# EntradasAnalogicas.net
KiCad netlist of a schematic drawn in Altium Designer
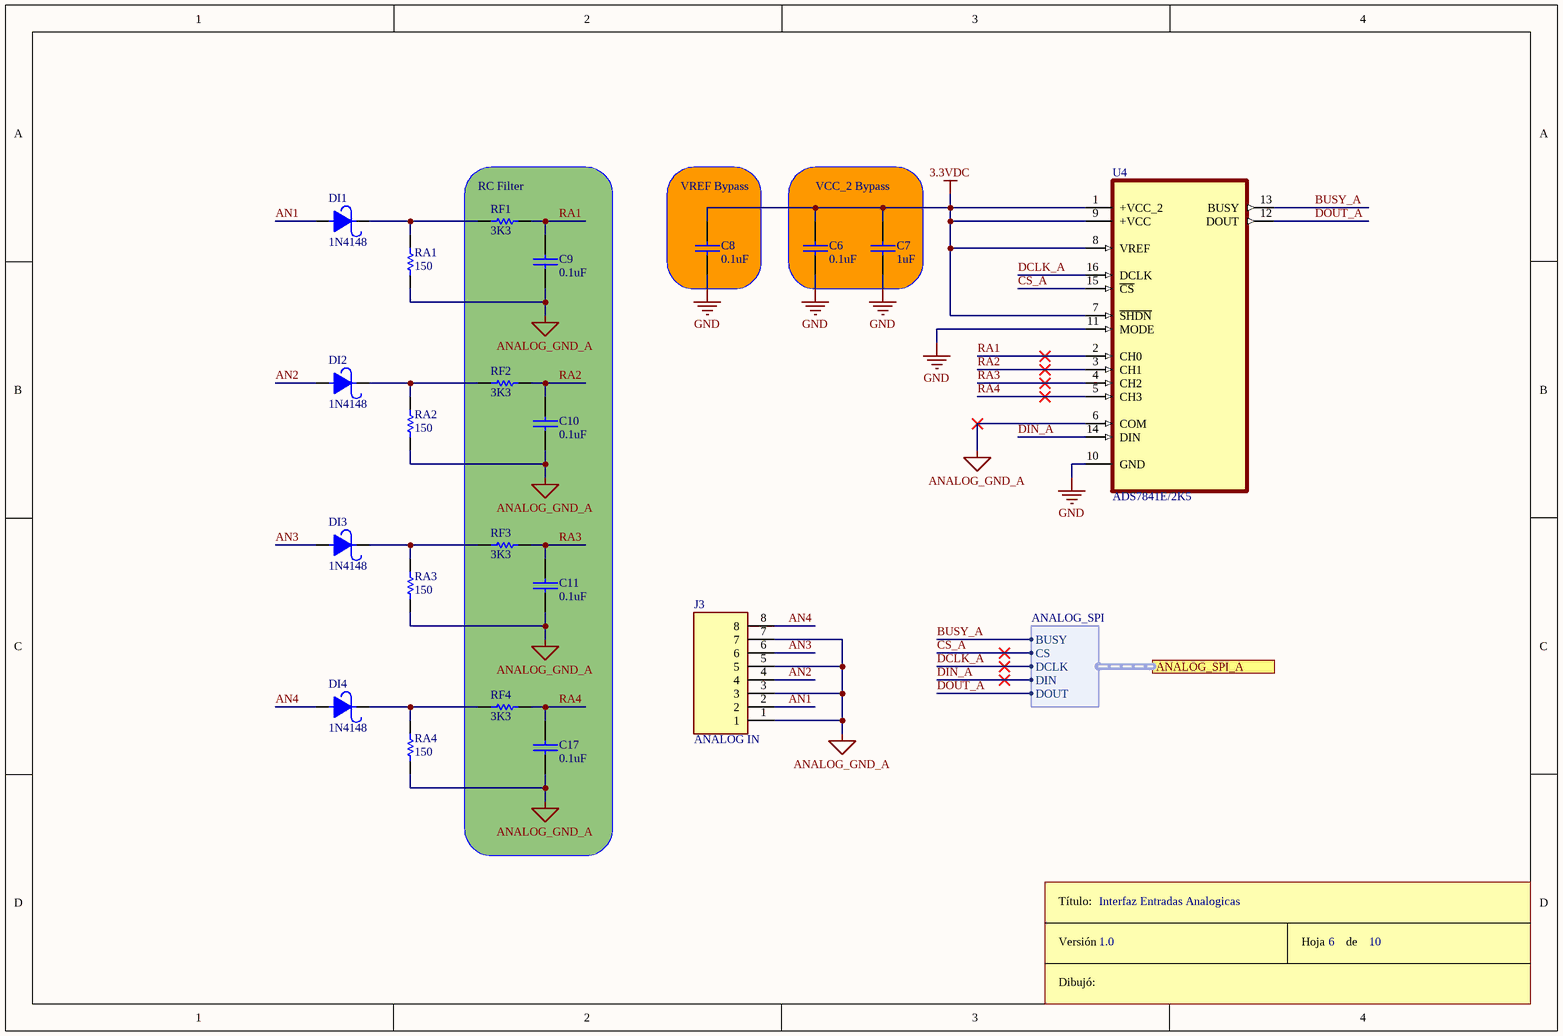
[diagram p0: EntradasAnalogicas.SchDoc]

(export (version "E")
  (design (tool "Eeschema 10.0.6"))
  (components
    (comp (ref "C6") (value "0.1uF") (footprint "CAP100") (libsource (lib "LIBEBAL") (part "CAP")))
    (comp (ref "C7") (value "1uF") (footprint "CAP200") (libsource (lib "LIBEBAL") (part "CAP")))
    (comp (ref "C8") (value "0.1uF") (footprint "CAP100") (libsource (lib "LIBEBAL") (part "CAP")))
    (comp (ref "C9") (value "0.1uF") (footprint "CAP100") (libsource (lib "LIBEBAL") (part "CAP")))
    (comp (ref "C10") (value "0.1uF") (footprint "CAP100") (libsource (lib "LIBEBAL") (part "CAP")))
    (comp (ref "C11") (value "0.1uF") (footprint "CAP100") (libsource (lib "LIBEBAL") (part "CAP")))
    (comp (ref "C17") (value "0.1uF") (footprint "CAP100") (libsource (lib "LIBEBAL") (part "CAP")))
    (comp (ref "DI1") (value "1N4148") (footprint "DO41") (libsource (lib "LIBEBAL") (part "DIODO SCHOTTKY")))
    (comp (ref "DI2") (value "1N4148") (footprint "DO41") (libsource (lib "LIBEBAL") (part "DIODO SCHOTTKY")))
    (comp (ref "DI3") (value "1N4148") (footprint "DO41") (libsource (lib "LIBEBAL") (part "DIODO SCHOTTKY")))
    (comp (ref "DI4") (value "1N4148") (footprint "DO41") (libsource (lib "LIBEBAL") (part "DIODO SCHOTTKY")))
    (comp (ref "J3")
      (value "ANALOG IN")
      (footprint "TE_1586863-8")
      (description "Conn Power HDR 8 POS 4.2mm Solder RA Thru-Hole 8 Terminal 1 Port Tray")
      (fields (field (name "MF") "TE Connectivity") (field (name "MP") "1586863-8"))
      (libsource (lib "MFW8R") (part "1586863-8"))
    )
    (comp (ref "RA1") (value "150") (footprint "RES300") (libsource (lib "LIBEBAL") (part "RES")))
    (comp (ref "RA2") (value "150") (footprint "RES300") (libsource (lib "LIBEBAL") (part "RES")))
    (comp (ref "RA3") (value "150") (footprint "RES300") (libsource (lib "LIBEBAL") (part "RES")))
    (comp (ref "RA4") (value "150") (footprint "RES300") (libsource (lib "LIBEBAL") (part "RES")))
    (comp (ref "RF1") (value "3K3") (footprint "RES300") (libsource (lib "LIBEBAL") (part "RES")))
    (comp (ref "RF2") (value "3K3") (footprint "RES300") (libsource (lib "LIBEBAL") (part "RES")))
    (comp (ref "RF3") (value "3K3") (footprint "RES300") (libsource (lib "LIBEBAL") (part "RES")))
    (comp (ref "RF4") (value "3K3") (footprint "RES300") (libsource (lib "LIBEBAL") (part "RES")))
    (comp (ref "ROT4") (value "Rótulo") (libsource (lib "LIB PIO IX") (part "Rótulo")))
    (comp (ref "U4")
      (value "ADS7841E/2K5")
      (footprint "SOP63P600X175-16N")
      (description "ANALOG-TO-DIGITAL CONVERTER")
      (libsource (lib "ADS7841E_2K5") (part "ADS7841E/2K5"))
    )
  )
  (nets
    (net (code "2") (name "/AN1") (class "Default")
      (node (ref "DI1") (pin "1") (pinfunction "1_1") (pintype "passive"))
      (node (ref "J3") (pin "2") (pinfunction "2_2") (pintype "passive"))
    )
    (net (code "3") (name "/AN2") (class "Default")
      (node (ref "DI2") (pin "1") (pinfunction "1_1") (pintype "passive"))
      (node (ref "J3") (pin "4") (pinfunction "4_4") (pintype "passive"))
    )
    (net (code "4") (name "/AN3") (class "Default")
      (node (ref "DI3") (pin "1") (pinfunction "1_1") (pintype "passive"))
      (node (ref "J3") (pin "6") (pinfunction "6_6") (pintype "passive"))
    )
    (net (code "5") (name "/AN4") (class "Default")
      (node (ref "DI4") (pin "1") (pinfunction "1_1") (pintype "passive"))
      (node (ref "J3") (pin "8") (pinfunction "8_8") (pintype "passive"))
    )
    (net (code "6") (name "/BUSY_A") (class "Default")
      (node (ref "U4") (pin "13") (pinfunction "BUSY_13") (pintype "output"))
    )
    (net (code "7") (name "/CS_A") (class "Default")
      (node (ref "U4") (pin "15") (pinfunction "~{CS}_15") (pintype "input"))
    )
    (net (code "8") (name "/DCLK_A") (class "Default")
      (node (ref "U4") (pin "16") (pinfunction "DCLK_16") (pintype "input"))
    )
    (net (code "9") (name "/DIN_A") (class "Default")
      (node (ref "U4") (pin "14") (pinfunction "DIN_14") (pintype "input"))
    )
    (net (code "10") (name "/DOUT_A") (class "Default")
      (node (ref "U4") (pin "12") (pinfunction "DOUT_12") (pintype "output"))
    )
    (net (code "11") (name "/RA1") (class "Default")
      (node (ref "C9") (pin "1") (pinfunction "1_1") (pintype "passive"))
      (node (ref "RF1") (pin "2") (pinfunction "2_2") (pintype "passive"))
      (node (ref "U4") (pin "2") (pinfunction "CH0_2") (pintype "input"))
    )
    (net (code "12") (name "/RA2") (class "Default")
      (node (ref "C10") (pin "1") (pinfunction "1_1") (pintype "passive"))
      (node (ref "RF2") (pin "2") (pinfunction "2_2") (pintype "passive"))
      (node (ref "U4") (pin "3") (pinfunction "CH1_3") (pintype "input"))
    )
    (net (code "13") (name "/RA3") (class "Default")
      (node (ref "C11") (pin "1") (pinfunction "1_1") (pintype "passive"))
      (node (ref "RF3") (pin "2") (pinfunction "2_2") (pintype "passive"))
      (node (ref "U4") (pin "4") (pinfunction "CH2_4") (pintype "input"))
    )
    (net (code "14") (name "/RA4") (class "Default")
      (node (ref "C17") (pin "1") (pinfunction "1_1") (pintype "passive"))
      (node (ref "RF4") (pin "2") (pinfunction "2_2") (pintype "passive"))
      (node (ref "U4") (pin "5") (pinfunction "CH3_5") (pintype "input"))
    )
    (net (code "16") (name "3.3VDC") (class "Default")
      (node (ref "C6") (pin "1") (pinfunction "1_1") (pintype "passive"))
      (node (ref "C7") (pin "1") (pinfunction "1_1") (pintype "passive"))
      (node (ref "C8") (pin "1") (pinfunction "1_1") (pintype "passive"))
      (node (ref "U4") (pin "1") (pinfunction "+VCC_2_1") (pintype "power_in"))
      (node (ref "U4") (pin "7") (pinfunction "~{SHDN}_7") (pintype "input"))
      (node (ref "U4") (pin "8") (pinfunction "VREF_8") (pintype "input"))
      (node (ref "U4") (pin "9") (pinfunction "+VCC_9") (pintype "power_in"))
    )
    (net (code "17") (name "ANALOG_GND_A") (class "Default")
      (node (ref "C10") (pin "2") (pinfunction "2_2") (pintype "passive"))
      (node (ref "C11") (pin "2") (pinfunction "2_2") (pintype "passive"))
      (node (ref "C17") (pin "2") (pinfunction "2_2") (pintype "passive"))
      (node (ref "C9") (pin "2") (pinfunction "2_2") (pintype "passive"))
      (node (ref "J3") (pin "1") (pinfunction "1_1") (pintype "passive"))
      (node (ref "J3") (pin "3") (pinfunction "3_3") (pintype "passive"))
      (node (ref "J3") (pin "5") (pinfunction "5_5") (pintype "passive"))
      (node (ref "J3") (pin "7") (pinfunction "7_7") (pintype "passive"))
      (node (ref "RA1") (pin "1") (pinfunction "1_1") (pintype "passive"))
      (node (ref "RA2") (pin "1") (pinfunction "1_1") (pintype "passive"))
      (node (ref "RA3") (pin "1") (pinfunction "1_1") (pintype "passive"))
      (node (ref "RA4") (pin "1") (pinfunction "1_1") (pintype "passive"))
      (node (ref "U4") (pin "6") (pinfunction "COM_6") (pintype "input"))
    )
    (net (code "18") (name "GND") (class "Default")
      (node (ref "C6") (pin "2") (pinfunction "2_2") (pintype "passive"))
      (node (ref "C7") (pin "2") (pinfunction "2_2") (pintype "passive"))
      (node (ref "C8") (pin "2") (pinfunction "2_2") (pintype "passive"))
      (node (ref "U4") (pin "10") (pinfunction "GND_10") (pintype "passive"))
      (node (ref "U4") (pin "11") (pinfunction "MODE_11") (pintype "input"))
    )
    (net (code "19") (name "Net-(DI1-Pad2)") (class "Default")
      (node (ref "DI1") (pin "2") (pinfunction "2_2") (pintype "passive"))
      (node (ref "RA1") (pin "2") (pinfunction "2_2") (pintype "passive"))
      (node (ref "RF1") (pin "1") (pinfunction "1_1") (pintype "passive"))
    )
    (net (code "20") (name "Net-(DI2-Pad2)") (class "Default")
      (node (ref "DI2") (pin "2") (pinfunction "2_2") (pintype "passive"))
      (node (ref "RA2") (pin "2") (pinfunction "2_2") (pintype "passive"))
      (node (ref "RF2") (pin "1") (pinfunction "1_1") (pintype "passive"))
    )
    (net (code "21") (name "Net-(DI3-Pad2)") (class "Default")
      (node (ref "DI3") (pin "2") (pinfunction "2_2") (pintype "passive"))
      (node (ref "RA3") (pin "2") (pinfunction "2_2") (pintype "passive"))
      (node (ref "RF3") (pin "1") (pinfunction "1_1") (pintype "passive"))
    )
    (net (code "22") (name "Net-(DI4-Pad2)") (class "Default")
      (node (ref "DI4") (pin "2") (pinfunction "2_2") (pintype "passive"))
      (node (ref "RA4") (pin "2") (pinfunction "2_2") (pintype "passive"))
      (node (ref "RF4") (pin "1") (pinfunction "1_1") (pintype "passive"))
    )
  )
)
